# Display.net
KiCad netlist of a schematic drawn in EAGLE
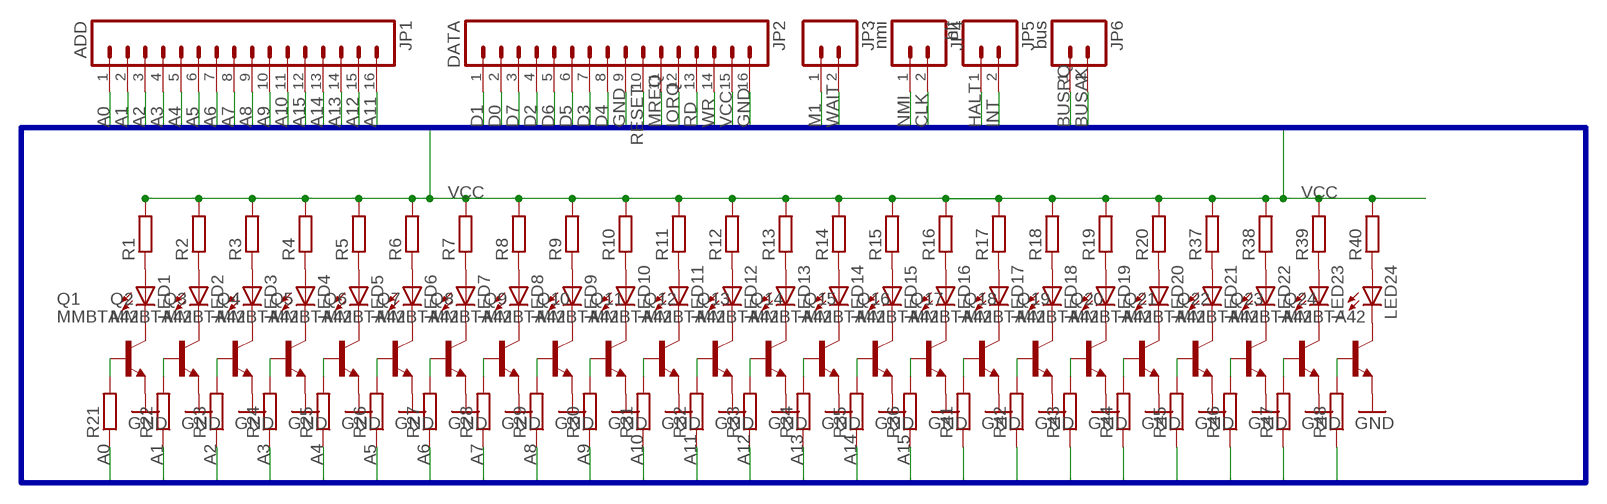
[diagram p0: schematic, sheet 1]

(export (version "E")
  (design (tool "Eeschema 10.0.6"))
  (components
    (comp (ref "JP1")
      (value "ADD")
      (footprint "eagle-import:1X16")
      (libsource (lib "eagle-import") (part "M16PTH"))
    )
    (comp (ref "JP2")
      (value "DATA")
      (footprint "eagle-import:1X16")
      (libsource (lib "eagle-import") (part "M16PTH"))
    )
    (comp (ref "JP3")
      (value "M02PTH")
      (footprint "eagle-import:1X02")
      (libsource (lib "eagle-import") (part "M02PTH"))
    )
    (comp (ref "JP4")
      (value "nmi")
      (footprint "eagle-import:1X02")
      (libsource (lib "eagle-import") (part "M02PTH"))
    )
    (comp (ref "JP5")
      (value "hlt")
      (footprint "eagle-import:1X02")
      (libsource (lib "eagle-import") (part "M02PTH"))
    )
    (comp (ref "JP6")
      (value "bus")
      (footprint "eagle-import:1X02")
      (libsource (lib "eagle-import") (part "M02PTH"))
    )
    (comp (ref "LED1")
      (value "LEDCHIP-LED0805")
      (footprint "eagle-import:CHIP-LED0805")
      (libsource (lib "eagle-import") (part "LEDCHIP-LED0805"))
    )
    (comp (ref "LED2")
      (value "LEDCHIP-LED0805")
      (footprint "eagle-import:CHIP-LED0805")
      (libsource (lib "eagle-import") (part "LEDCHIP-LED0805"))
    )
    (comp (ref "LED3")
      (value "LEDCHIP-LED0805")
      (footprint "eagle-import:CHIP-LED0805")
      (libsource (lib "eagle-import") (part "LEDCHIP-LED0805"))
    )
    (comp (ref "LED4")
      (value "LEDCHIP-LED0805")
      (footprint "eagle-import:CHIP-LED0805")
      (libsource (lib "eagle-import") (part "LEDCHIP-LED0805"))
    )
    (comp (ref "LED5")
      (value "LEDCHIP-LED0805")
      (footprint "eagle-import:CHIP-LED0805")
      (libsource (lib "eagle-import") (part "LEDCHIP-LED0805"))
    )
    (comp (ref "LED6")
      (value "LEDCHIP-LED0805")
      (footprint "eagle-import:CHIP-LED0805")
      (libsource (lib "eagle-import") (part "LEDCHIP-LED0805"))
    )
    (comp (ref "LED7")
      (value "LEDCHIP-LED0805")
      (footprint "eagle-import:CHIP-LED0805")
      (libsource (lib "eagle-import") (part "LEDCHIP-LED0805"))
    )
    (comp (ref "LED8")
      (value "LEDCHIP-LED0805")
      (footprint "eagle-import:CHIP-LED0805")
      (libsource (lib "eagle-import") (part "LEDCHIP-LED0805"))
    )
    (comp (ref "LED9")
      (value "LEDCHIP-LED0805")
      (footprint "eagle-import:CHIP-LED0805")
      (libsource (lib "eagle-import") (part "LEDCHIP-LED0805"))
    )
    (comp (ref "LED10")
      (value "LEDCHIP-LED0805")
      (footprint "eagle-import:CHIP-LED0805")
      (libsource (lib "eagle-import") (part "LEDCHIP-LED0805"))
    )
    (comp (ref "LED11")
      (value "LEDCHIP-LED0805")
      (footprint "eagle-import:CHIP-LED0805")
      (libsource (lib "eagle-import") (part "LEDCHIP-LED0805"))
    )
    (comp (ref "LED12")
      (value "LEDCHIP-LED0805")
      (footprint "eagle-import:CHIP-LED0805")
      (libsource (lib "eagle-import") (part "LEDCHIP-LED0805"))
    )
    (comp (ref "LED13")
      (value "LEDCHIP-LED0805")
      (footprint "eagle-import:CHIP-LED0805")
      (libsource (lib "eagle-import") (part "LEDCHIP-LED0805"))
    )
    (comp (ref "LED14")
      (value "LEDCHIP-LED0805")
      (footprint "eagle-import:CHIP-LED0805")
      (libsource (lib "eagle-import") (part "LEDCHIP-LED0805"))
    )
    (comp (ref "LED15")
      (value "LEDCHIP-LED0805")
      (footprint "eagle-import:CHIP-LED0805")
      (libsource (lib "eagle-import") (part "LEDCHIP-LED0805"))
    )
    (comp (ref "LED16")
      (value "LEDCHIP-LED0805")
      (footprint "eagle-import:CHIP-LED0805")
      (libsource (lib "eagle-import") (part "LEDCHIP-LED0805"))
    )
    (comp (ref "LED17")
      (value "LEDCHIP-LED0805")
      (footprint "eagle-import:CHIP-LED0805")
      (libsource (lib "eagle-import") (part "LEDCHIP-LED0805"))
    )
    (comp (ref "LED18")
      (value "LEDCHIP-LED0805")
      (footprint "eagle-import:CHIP-LED0805")
      (libsource (lib "eagle-import") (part "LEDCHIP-LED0805"))
    )
    (comp (ref "LED19")
      (value "LEDCHIP-LED0805")
      (footprint "eagle-import:CHIP-LED0805")
      (libsource (lib "eagle-import") (part "LEDCHIP-LED0805"))
    )
    (comp (ref "LED20")
      (value "LEDCHIP-LED0805")
      (footprint "eagle-import:CHIP-LED0805")
      (libsource (lib "eagle-import") (part "LEDCHIP-LED0805"))
    )
    (comp (ref "LED21")
      (value "LEDCHIP-LED0805")
      (footprint "eagle-import:CHIP-LED0805")
      (libsource (lib "eagle-import") (part "LEDCHIP-LED0805"))
    )
    (comp (ref "LED22")
      (value "LEDCHIP-LED0805")
      (footprint "eagle-import:CHIP-LED0805")
      (libsource (lib "eagle-import") (part "LEDCHIP-LED0805"))
    )
    (comp (ref "LED23")
      (value "LEDCHIP-LED0805")
      (footprint "eagle-import:CHIP-LED0805")
      (libsource (lib "eagle-import") (part "LEDCHIP-LED0805"))
    )
    (comp (ref "LED24")
      (value "LEDCHIP-LED0805")
      (footprint "eagle-import:CHIP-LED0805")
      (libsource (lib "eagle-import") (part "LEDCHIP-LED0805"))
    )
    (comp (ref "Q1")
      (value "MMBTA42")
      (footprint "eagle-import:SOT23")
      (libsource (lib "eagle-import") (part "MMBTA42"))
    )
    (comp (ref "Q2")
      (value "MMBTA42")
      (footprint "eagle-import:SOT23")
      (libsource (lib "eagle-import") (part "MMBTA42"))
    )
    (comp (ref "Q3")
      (value "MMBTA42")
      (footprint "eagle-import:SOT23")
      (libsource (lib "eagle-import") (part "MMBTA42"))
    )
    (comp (ref "Q4")
      (value "MMBTA42")
      (footprint "eagle-import:SOT23")
      (libsource (lib "eagle-import") (part "MMBTA42"))
    )
    (comp (ref "Q5")
      (value "MMBTA42")
      (footprint "eagle-import:SOT23")
      (libsource (lib "eagle-import") (part "MMBTA42"))
    )
    (comp (ref "Q6")
      (value "MMBTA42")
      (footprint "eagle-import:SOT23")
      (libsource (lib "eagle-import") (part "MMBTA42"))
    )
    (comp (ref "Q7")
      (value "MMBTA42")
      (footprint "eagle-import:SOT23")
      (libsource (lib "eagle-import") (part "MMBTA42"))
    )
    (comp (ref "Q8")
      (value "MMBTA42")
      (footprint "eagle-import:SOT23")
      (libsource (lib "eagle-import") (part "MMBTA42"))
    )
    (comp (ref "Q9")
      (value "MMBTA42")
      (footprint "eagle-import:SOT23")
      (libsource (lib "eagle-import") (part "MMBTA42"))
    )
    (comp (ref "Q10")
      (value "MMBTA42")
      (footprint "eagle-import:SOT23")
      (libsource (lib "eagle-import") (part "MMBTA42"))
    )
    (comp (ref "Q11")
      (value "MMBTA42")
      (footprint "eagle-import:SOT23")
      (libsource (lib "eagle-import") (part "MMBTA42"))
    )
    (comp (ref "Q12")
      (value "MMBTA42")
      (footprint "eagle-import:SOT23")
      (libsource (lib "eagle-import") (part "MMBTA42"))
    )
    (comp (ref "Q13")
      (value "MMBTA42")
      (footprint "eagle-import:SOT23")
      (libsource (lib "eagle-import") (part "MMBTA42"))
    )
    (comp (ref "Q14")
      (value "MMBTA42")
      (footprint "eagle-import:SOT23")
      (libsource (lib "eagle-import") (part "MMBTA42"))
    )
    (comp (ref "Q15")
      (value "MMBTA42")
      (footprint "eagle-import:SOT23")
      (libsource (lib "eagle-import") (part "MMBTA42"))
    )
    (comp (ref "Q16")
      (value "MMBTA42")
      (footprint "eagle-import:SOT23")
      (libsource (lib "eagle-import") (part "MMBTA42"))
    )
    (comp (ref "Q17")
      (value "MMBTA42")
      (footprint "eagle-import:SOT23")
      (libsource (lib "eagle-import") (part "MMBTA42"))
    )
    (comp (ref "Q18")
      (value "MMBTA42")
      (footprint "eagle-import:SOT23")
      (libsource (lib "eagle-import") (part "MMBTA42"))
    )
    (comp (ref "Q19")
      (value "MMBTA42")
      (footprint "eagle-import:SOT23")
      (libsource (lib "eagle-import") (part "MMBTA42"))
    )
    (comp (ref "Q20")
      (value "MMBTA42")
      (footprint "eagle-import:SOT23")
      (libsource (lib "eagle-import") (part "MMBTA42"))
    )
    (comp (ref "Q21")
      (value "MMBTA42")
      (footprint "eagle-import:SOT23")
      (libsource (lib "eagle-import") (part "MMBTA42"))
    )
    (comp (ref "Q22")
      (value "MMBTA42")
      (footprint "eagle-import:SOT23")
      (libsource (lib "eagle-import") (part "MMBTA42"))
    )
    (comp (ref "Q23")
      (value "MMBTA42")
      (footprint "eagle-import:SOT23")
      (libsource (lib "eagle-import") (part "MMBTA42"))
    )
    (comp (ref "Q24")
      (value "MMBTA42")
      (footprint "eagle-import:SOT23")
      (libsource (lib "eagle-import") (part "MMBTA42"))
    )
    (comp (ref "R1")
      (value "R-EU_M0805")
      (footprint "eagle-import:M0805")
      (libsource (lib "eagle-import") (part "R-EU_M0805"))
    )
    (comp (ref "R2")
      (value "R-EU_M0805")
      (footprint "eagle-import:M0805")
      (libsource (lib "eagle-import") (part "R-EU_M0805"))
    )
    (comp (ref "R3")
      (value "R-EU_M0805")
      (footprint "eagle-import:M0805")
      (libsource (lib "eagle-import") (part "R-EU_M0805"))
    )
    (comp (ref "R4")
      (value "R-EU_M0805")
      (footprint "eagle-import:M0805")
      (libsource (lib "eagle-import") (part "R-EU_M0805"))
    )
    (comp (ref "R5")
      (value "R-EU_M0805")
      (footprint "eagle-import:M0805")
      (libsource (lib "eagle-import") (part "R-EU_M0805"))
    )
    (comp (ref "R6")
      (value "R-EU_M0805")
      (footprint "eagle-import:M0805")
      (libsource (lib "eagle-import") (part "R-EU_M0805"))
    )
    (comp (ref "R7")
      (value "R-EU_M0805")
      (footprint "eagle-import:M0805")
      (libsource (lib "eagle-import") (part "R-EU_M0805"))
    )
    (comp (ref "R8")
      (value "R-EU_M0805")
      (footprint "eagle-import:M0805")
      (libsource (lib "eagle-import") (part "R-EU_M0805"))
    )
    (comp (ref "R9")
      (value "R-EU_M0805")
      (footprint "eagle-import:M0805")
      (libsource (lib "eagle-import") (part "R-EU_M0805"))
    )
    (comp (ref "R10")
      (value "R-EU_M0805")
      (footprint "eagle-import:M0805")
      (libsource (lib "eagle-import") (part "R-EU_M0805"))
    )
    (comp (ref "R11")
      (value "R-EU_M0805")
      (footprint "eagle-import:M0805")
      (libsource (lib "eagle-import") (part "R-EU_M0805"))
    )
    (comp (ref "R12")
      (value "R-EU_M0805")
      (footprint "eagle-import:M0805")
      (libsource (lib "eagle-import") (part "R-EU_M0805"))
    )
    (comp (ref "R13")
      (value "R-EU_M0805")
      (footprint "eagle-import:M0805")
      (libsource (lib "eagle-import") (part "R-EU_M0805"))
    )
    (comp (ref "R14")
      (value "R-EU_M0805")
      (footprint "eagle-import:M0805")
      (libsource (lib "eagle-import") (part "R-EU_M0805"))
    )
    (comp (ref "R15")
      (value "R-EU_M0805")
      (footprint "eagle-import:M0805")
      (libsource (lib "eagle-import") (part "R-EU_M0805"))
    )
    (comp (ref "R16")
      (value "R-EU_M0805")
      (footprint "eagle-import:M0805")
      (libsource (lib "eagle-import") (part "R-EU_M0805"))
    )
    (comp (ref "R17")
      (value "R-EU_M0805")
      (footprint "eagle-import:M0805")
      (libsource (lib "eagle-import") (part "R-EU_M0805"))
    )
    (comp (ref "R18")
      (value "R-EU_M0805")
      (footprint "eagle-import:M0805")
      (libsource (lib "eagle-import") (part "R-EU_M0805"))
    )
    (comp (ref "R19")
      (value "R-EU_M0805")
      (footprint "eagle-import:M0805")
      (libsource (lib "eagle-import") (part "R-EU_M0805"))
    )
    (comp (ref "R20")
      (value "R-EU_M0805")
      (footprint "eagle-import:M0805")
      (libsource (lib "eagle-import") (part "R-EU_M0805"))
    )
    (comp (ref "R21")
      (value "R-EU_M0805")
      (footprint "eagle-import:M0805")
      (libsource (lib "eagle-import") (part "R-EU_M0805"))
    )
    (comp (ref "R22")
      (value "R-EU_M0805")
      (footprint "eagle-import:M0805")
      (libsource (lib "eagle-import") (part "R-EU_M0805"))
    )
    (comp (ref "R23")
      (value "R-EU_M0805")
      (footprint "eagle-import:M0805")
      (libsource (lib "eagle-import") (part "R-EU_M0805"))
    )
    (comp (ref "R24")
      (value "R-EU_M0805")
      (footprint "eagle-import:M0805")
      (libsource (lib "eagle-import") (part "R-EU_M0805"))
    )
    (comp (ref "R25")
      (value "R-EU_M0805")
      (footprint "eagle-import:M0805")
      (libsource (lib "eagle-import") (part "R-EU_M0805"))
    )
    (comp (ref "R26")
      (value "R-EU_M0805")
      (footprint "eagle-import:M0805")
      (libsource (lib "eagle-import") (part "R-EU_M0805"))
    )
    (comp (ref "R27")
      (value "R-EU_M0805")
      (footprint "eagle-import:M0805")
      (libsource (lib "eagle-import") (part "R-EU_M0805"))
    )
    (comp (ref "R28")
      (value "R-EU_M0805")
      (footprint "eagle-import:M0805")
      (libsource (lib "eagle-import") (part "R-EU_M0805"))
    )
    (comp (ref "R29")
      (value "R-EU_M0805")
      (footprint "eagle-import:M0805")
      (libsource (lib "eagle-import") (part "R-EU_M0805"))
    )
    (comp (ref "R30")
      (value "R-EU_M0805")
      (footprint "eagle-import:M0805")
      (libsource (lib "eagle-import") (part "R-EU_M0805"))
    )
    (comp (ref "R31")
      (value "R-EU_M0805")
      (footprint "eagle-import:M0805")
      (libsource (lib "eagle-import") (part "R-EU_M0805"))
    )
    (comp (ref "R32")
      (value "R-EU_M0805")
      (footprint "eagle-import:M0805")
      (libsource (lib "eagle-import") (part "R-EU_M0805"))
    )
    (comp (ref "R33")
      (value "R-EU_M0805")
      (footprint "eagle-import:M0805")
      (libsource (lib "eagle-import") (part "R-EU_M0805"))
    )
    (comp (ref "R34")
      (value "R-EU_M0805")
      (footprint "eagle-import:M0805")
      (libsource (lib "eagle-import") (part "R-EU_M0805"))
    )
    (comp (ref "R35")
      (value "R-EU_M0805")
      (footprint "eagle-import:M0805")
      (libsource (lib "eagle-import") (part "R-EU_M0805"))
    )
    (comp (ref "R36")
      (value "R-EU_M0805")
      (footprint "eagle-import:M0805")
      (libsource (lib "eagle-import") (part "R-EU_M0805"))
    )
    (comp (ref "R37")
      (value "R-EU_M0805")
      (footprint "eagle-import:M0805")
      (libsource (lib "eagle-import") (part "R-EU_M0805"))
    )
    (comp (ref "R38")
      (value "R-EU_M0805")
      (footprint "eagle-import:M0805")
      (libsource (lib "eagle-import") (part "R-EU_M0805"))
    )
    (comp (ref "R39")
      (value "R-EU_M0805")
      (footprint "eagle-import:M0805")
      (libsource (lib "eagle-import") (part "R-EU_M0805"))
    )
    (comp (ref "R40")
      (value "R-EU_M0805")
      (footprint "eagle-import:M0805")
      (libsource (lib "eagle-import") (part "R-EU_M0805"))
    )
    (comp (ref "R41")
      (value "R-EU_M0805")
      (footprint "eagle-import:M0805")
      (libsource (lib "eagle-import") (part "R-EU_M0805"))
    )
    (comp (ref "R42")
      (value "R-EU_M0805")
      (footprint "eagle-import:M0805")
      (libsource (lib "eagle-import") (part "R-EU_M0805"))
    )
    (comp (ref "R43")
      (value "R-EU_M0805")
      (footprint "eagle-import:M0805")
      (libsource (lib "eagle-import") (part "R-EU_M0805"))
    )
    (comp (ref "R44")
      (value "R-EU_M0805")
      (footprint "eagle-import:M0805")
      (libsource (lib "eagle-import") (part "R-EU_M0805"))
    )
    (comp (ref "R45")
      (value "R-EU_M0805")
      (footprint "eagle-import:M0805")
      (libsource (lib "eagle-import") (part "R-EU_M0805"))
    )
    (comp (ref "R46")
      (value "R-EU_M0805")
      (footprint "eagle-import:M0805")
      (libsource (lib "eagle-import") (part "R-EU_M0805"))
    )
    (comp (ref "R47")
      (value "R-EU_M0805")
      (footprint "eagle-import:M0805")
      (libsource (lib "eagle-import") (part "R-EU_M0805"))
    )
    (comp (ref "R48")
      (value "R-EU_M0805")
      (footprint "eagle-import:M0805")
      (libsource (lib "eagle-import") (part "R-EU_M0805"))
    )
  )
  (nets
    (net (code "1") (name "/A0") (class "Default")
      (node (ref "JP1") (pin "1") (pinfunction "1_1") (pintype "passive"))
      (node (ref "R21") (pin "1") (pinfunction "1_1") (pintype "passive"))
    )
    (net (code "2") (name "/A1") (class "Default")
      (node (ref "JP1") (pin "2") (pinfunction "2_2") (pintype "passive"))
      (node (ref "R22") (pin "1") (pinfunction "1_1") (pintype "passive"))
    )
    (net (code "3") (name "/A2") (class "Default")
      (node (ref "JP1") (pin "3") (pinfunction "3_3") (pintype "passive"))
      (node (ref "R23") (pin "1") (pinfunction "1_1") (pintype "passive"))
    )
    (net (code "4") (name "/A3") (class "Default")
      (node (ref "JP1") (pin "4") (pinfunction "4_4") (pintype "passive"))
      (node (ref "R24") (pin "1") (pinfunction "1_1") (pintype "passive"))
    )
    (net (code "5") (name "/A4") (class "Default")
      (node (ref "JP1") (pin "5") (pinfunction "5_5") (pintype "passive"))
      (node (ref "R25") (pin "1") (pinfunction "1_1") (pintype "passive"))
    )
    (net (code "6") (name "/A5") (class "Default")
      (node (ref "JP1") (pin "6") (pinfunction "6_6") (pintype "passive"))
      (node (ref "R26") (pin "1") (pinfunction "1_1") (pintype "passive"))
    )
    (net (code "7") (name "/A6") (class "Default")
      (node (ref "JP1") (pin "7") (pinfunction "7_7") (pintype "passive"))
      (node (ref "R27") (pin "1") (pinfunction "1_1") (pintype "passive"))
    )
    (net (code "8") (name "/A7") (class "Default")
      (node (ref "JP1") (pin "8") (pinfunction "8_8") (pintype "passive"))
      (node (ref "R28") (pin "1") (pinfunction "1_1") (pintype "passive"))
    )
    (net (code "9") (name "/A8") (class "Default")
      (node (ref "JP1") (pin "9") (pinfunction "9_9") (pintype "passive"))
      (node (ref "R29") (pin "1") (pinfunction "1_1") (pintype "passive"))
    )
    (net (code "10") (name "/A9") (class "Default")
      (node (ref "JP1") (pin "10") (pinfunction "10_10") (pintype "passive"))
      (node (ref "R30") (pin "1") (pinfunction "1_1") (pintype "passive"))
    )
    (net (code "11") (name "/A10") (class "Default")
      (node (ref "JP1") (pin "11") (pinfunction "11_11") (pintype "passive"))
      (node (ref "R31") (pin "1") (pinfunction "1_1") (pintype "passive"))
    )
    (net (code "12") (name "/A11") (class "Default")
      (node (ref "JP1") (pin "16") (pinfunction "16_16") (pintype "passive"))
      (node (ref "R32") (pin "1") (pinfunction "1_1") (pintype "passive"))
    )
    (net (code "13") (name "/A12") (class "Default")
      (node (ref "JP1") (pin "15") (pinfunction "15_15") (pintype "passive"))
      (node (ref "R33") (pin "1") (pinfunction "1_1") (pintype "passive"))
    )
    (net (code "14") (name "/A13") (class "Default")
      (node (ref "JP1") (pin "14") (pinfunction "14_14") (pintype "passive"))
      (node (ref "R34") (pin "1") (pinfunction "1_1") (pintype "passive"))
    )
    (net (code "15") (name "/A14") (class "Default")
      (node (ref "JP1") (pin "13") (pinfunction "13_13") (pintype "passive"))
      (node (ref "R35") (pin "1") (pinfunction "1_1") (pintype "passive"))
    )
    (net (code "16") (name "/A15") (class "Default")
      (node (ref "JP1") (pin "12") (pinfunction "12_12") (pintype "passive"))
      (node (ref "R36") (pin "1") (pinfunction "1_1") (pintype "passive"))
    )
    (net (code "17") (name "/BUSAK") (class "Default")
      (node (ref "JP6") (pin "2") (pinfunction "2_2") (pintype "passive"))
    )
    (net (code "18") (name "/BUSRQ") (class "Default")
      (node (ref "JP6") (pin "1") (pinfunction "1_1") (pintype "passive"))
    )
    (net (code "19") (name "/CLK") (class "Default")
      (node (ref "JP4") (pin "2") (pinfunction "2_2") (pintype "passive"))
    )
    (net (code "20") (name "/D0") (class "Default")
      (node (ref "JP2") (pin "2") (pinfunction "2_2") (pintype "passive"))
      (node (ref "R41") (pin "1") (pinfunction "1_1") (pintype "passive"))
    )
    (net (code "21") (name "/D1") (class "Default")
      (node (ref "JP2") (pin "1") (pinfunction "1_1") (pintype "passive"))
      (node (ref "R42") (pin "1") (pinfunction "1_1") (pintype "passive"))
    )
    (net (code "22") (name "/D2") (class "Default")
      (node (ref "JP2") (pin "4") (pinfunction "4_4") (pintype "passive"))
      (node (ref "R43") (pin "1") (pinfunction "1_1") (pintype "passive"))
    )
    (net (code "23") (name "/D3") (class "Default")
      (node (ref "JP2") (pin "7") (pinfunction "7_7") (pintype "passive"))
      (node (ref "R44") (pin "1") (pinfunction "1_1") (pintype "passive"))
    )
    (net (code "24") (name "/D4") (class "Default")
      (node (ref "JP2") (pin "8") (pinfunction "8_8") (pintype "passive"))
      (node (ref "R45") (pin "1") (pinfunction "1_1") (pintype "passive"))
    )
    (net (code "25") (name "/D5") (class "Default")
      (node (ref "JP2") (pin "6") (pinfunction "6_6") (pintype "passive"))
      (node (ref "R46") (pin "1") (pinfunction "1_1") (pintype "passive"))
    )
    (net (code "26") (name "/D6") (class "Default")
      (node (ref "JP2") (pin "5") (pinfunction "5_5") (pintype "passive"))
      (node (ref "R47") (pin "1") (pinfunction "1_1") (pintype "passive"))
    )
    (net (code "27") (name "/D7") (class "Default")
      (node (ref "JP2") (pin "3") (pinfunction "3_3") (pintype "passive"))
      (node (ref "R48") (pin "1") (pinfunction "1_1") (pintype "passive"))
    )
    (net (code "28") (name "/HALT") (class "Default")
      (node (ref "JP5") (pin "1") (pinfunction "1_1") (pintype "passive"))
    )
    (net (code "29") (name "/INT") (class "Default")
      (node (ref "JP5") (pin "2") (pinfunction "2_2") (pintype "passive"))
    )
    (net (code "30") (name "/IORQ") (class "Default")
      (node (ref "JP2") (pin "12") (pinfunction "12_12") (pintype "passive"))
    )
    (net (code "31") (name "/M1") (class "Default")
      (node (ref "JP3") (pin "1") (pinfunction "1_1") (pintype "passive"))
    )
    (net (code "32") (name "/MREQ") (class "Default")
      (node (ref "JP2") (pin "11") (pinfunction "11_11") (pintype "passive"))
    )
    (net (code "33") (name "/NMI") (class "Default")
      (node (ref "JP4") (pin "1") (pinfunction "1_1") (pintype "passive"))
    )
    (net (code "34") (name "/RD") (class "Default")
      (node (ref "JP2") (pin "13") (pinfunction "13_13") (pintype "passive"))
    )
    (net (code "35") (name "/RESET") (class "Default")
      (node (ref "JP2") (pin "10") (pinfunction "10_10") (pintype "passive"))
    )
    (net (code "36") (name "/VCC") (class "Default")
      (node (ref "JP2") (pin "15") (pinfunction "15_15") (pintype "passive"))
      (node (ref "R1") (pin "2") (pinfunction "2_2") (pintype "passive"))
      (node (ref "R10") (pin "2") (pinfunction "2_2") (pintype "passive"))
      (node (ref "R11") (pin "2") (pinfunction "2_2") (pintype "passive"))
      (node (ref "R12") (pin "2") (pinfunction "2_2") (pintype "passive"))
      (node (ref "R13") (pin "2") (pinfunction "2_2") (pintype "passive"))
      (node (ref "R14") (pin "2") (pinfunction "2_2") (pintype "passive"))
      (node (ref "R15") (pin "2") (pinfunction "2_2") (pintype "passive"))
      (node (ref "R16") (pin "2") (pinfunction "2_2") (pintype "passive"))
      (node (ref "R17") (pin "2") (pinfunction "2_2") (pintype "passive"))
      (node (ref "R18") (pin "2") (pinfunction "2_2") (pintype "passive"))
      (node (ref "R19") (pin "2") (pinfunction "2_2") (pintype "passive"))
      (node (ref "R2") (pin "2") (pinfunction "2_2") (pintype "passive"))
      (node (ref "R20") (pin "2") (pinfunction "2_2") (pintype "passive"))
      (node (ref "R3") (pin "2") (pinfunction "2_2") (pintype "passive"))
      (node (ref "R37") (pin "2") (pinfunction "2_2") (pintype "passive"))
      (node (ref "R38") (pin "2") (pinfunction "2_2") (pintype "passive"))
      (node (ref "R39") (pin "2") (pinfunction "2_2") (pintype "passive"))
      (node (ref "R4") (pin "2") (pinfunction "2_2") (pintype "passive"))
      (node (ref "R40") (pin "2") (pinfunction "2_2") (pintype "passive"))
      (node (ref "R5") (pin "2") (pinfunction "2_2") (pintype "passive"))
      (node (ref "R6") (pin "2") (pinfunction "2_2") (pintype "passive"))
      (node (ref "R7") (pin "2") (pinfunction "2_2") (pintype "passive"))
      (node (ref "R8") (pin "2") (pinfunction "2_2") (pintype "passive"))
      (node (ref "R9") (pin "2") (pinfunction "2_2") (pintype "passive"))
    )
    (net (code "37") (name "/WAIT") (class "Default")
      (node (ref "JP3") (pin "2") (pinfunction "2_2") (pintype "passive"))
    )
    (net (code "38") (name "/WR") (class "Default")
      (node (ref "JP2") (pin "14") (pinfunction "14_14") (pintype "passive"))
    )
    (net (code "39") (name "GND") (class "Default")
      (node (ref "JP2") (pin "16") (pinfunction "16_16") (pintype "passive"))
      (node (ref "JP2") (pin "9") (pinfunction "9_9") (pintype "passive"))
      (node (ref "Q1") (pin "2") (pinfunction "E_2") (pintype "passive"))
      (node (ref "Q10") (pin "2") (pinfunction "E_2") (pintype "passive"))
      (node (ref "Q11") (pin "2") (pinfunction "E_2") (pintype "passive"))
      (node (ref "Q12") (pin "2") (pinfunction "E_2") (pintype "passive"))
      (node (ref "Q13") (pin "2") (pinfunction "E_2") (pintype "passive"))
      (node (ref "Q14") (pin "2") (pinfunction "E_2") (pintype "passive"))
      (node (ref "Q15") (pin "2") (pinfunction "E_2") (pintype "passive"))
      (node (ref "Q16") (pin "2") (pinfunction "E_2") (pintype "passive"))
      (node (ref "Q17") (pin "2") (pinfunction "E_2") (pintype "passive"))
      (node (ref "Q18") (pin "2") (pinfunction "E_2") (pintype "passive"))
      (node (ref "Q19") (pin "2") (pinfunction "E_2") (pintype "passive"))
      (node (ref "Q2") (pin "2") (pinfunction "E_2") (pintype "passive"))
      (node (ref "Q20") (pin "2") (pinfunction "E_2") (pintype "passive"))
      (node (ref "Q21") (pin "2") (pinfunction "E_2") (pintype "passive"))
      (node (ref "Q22") (pin "2") (pinfunction "E_2") (pintype "passive"))
      (node (ref "Q23") (pin "2") (pinfunction "E_2") (pintype "passive"))
      (node (ref "Q24") (pin "2") (pinfunction "E_2") (pintype "passive"))
      (node (ref "Q3") (pin "2") (pinfunction "E_2") (pintype "passive"))
      (node (ref "Q4") (pin "2") (pinfunction "E_2") (pintype "passive"))
      (node (ref "Q5") (pin "2") (pinfunction "E_2") (pintype "passive"))
      (node (ref "Q6") (pin "2") (pinfunction "E_2") (pintype "passive"))
      (node (ref "Q7") (pin "2") (pinfunction "E_2") (pintype "passive"))
      (node (ref "Q8") (pin "2") (pinfunction "E_2") (pintype "passive"))
      (node (ref "Q9") (pin "2") (pinfunction "E_2") (pintype "passive"))
    )
    (net (code "40") (name "Net-(LED1-PadA)") (class "Default")
      (node (ref "LED1") (pin "A") (pinfunction "A_A") (pintype "passive"))
      (node (ref "R1") (pin "1") (pinfunction "1_1") (pintype "passive"))
    )
    (net (code "41") (name "Net-(LED2-PadA)") (class "Default")
      (node (ref "LED2") (pin "A") (pinfunction "A_A") (pintype "passive"))
      (node (ref "R2") (pin "1") (pinfunction "1_1") (pintype "passive"))
    )
    (net (code "42") (name "Net-(LED3-PadA)") (class "Default")
      (node (ref "LED3") (pin "A") (pinfunction "A_A") (pintype "passive"))
      (node (ref "R3") (pin "1") (pinfunction "1_1") (pintype "passive"))
    )
    (net (code "43") (name "Net-(LED4-PadA)") (class "Default")
      (node (ref "LED4") (pin "A") (pinfunction "A_A") (pintype "passive"))
      (node (ref "R4") (pin "1") (pinfunction "1_1") (pintype "passive"))
    )
    (net (code "44") (name "Net-(LED5-PadA)") (class "Default")
      (node (ref "LED5") (pin "A") (pinfunction "A_A") (pintype "passive"))
      (node (ref "R5") (pin "1") (pinfunction "1_1") (pintype "passive"))
    )
    (net (code "45") (name "Net-(LED6-PadA)") (class "Default")
      (node (ref "LED6") (pin "A") (pinfunction "A_A") (pintype "passive"))
      (node (ref "R6") (pin "1") (pinfunction "1_1") (pintype "passive"))
    )
    (net (code "46") (name "Net-(LED7-PadA)") (class "Default")
      (node (ref "LED7") (pin "A") (pinfunction "A_A") (pintype "passive"))
      (node (ref "R7") (pin "1") (pinfunction "1_1") (pintype "passive"))
    )
    (net (code "47") (name "Net-(LED8-PadA)") (class "Default")
      (node (ref "LED8") (pin "A") (pinfunction "A_A") (pintype "passive"))
      (node (ref "R8") (pin "1") (pinfunction "1_1") (pintype "passive"))
    )
    (net (code "48") (name "Net-(LED9-PadA)") (class "Default")
      (node (ref "LED9") (pin "A") (pinfunction "A_A") (pintype "passive"))
      (node (ref "R9") (pin "1") (pinfunction "1_1") (pintype "passive"))
    )
    (net (code "49") (name "Net-(LED10-PadA)") (class "Default")
      (node (ref "LED10") (pin "A") (pinfunction "A_A") (pintype "passive"))
      (node (ref "R10") (pin "1") (pinfunction "1_1") (pintype "passive"))
    )
    (net (code "50") (name "Net-(LED11-PadA)") (class "Default")
      (node (ref "LED11") (pin "A") (pinfunction "A_A") (pintype "passive"))
      (node (ref "R11") (pin "1") (pinfunction "1_1") (pintype "passive"))
    )
    (net (code "51") (name "Net-(LED12-PadA)") (class "Default")
      (node (ref "LED12") (pin "A") (pinfunction "A_A") (pintype "passive"))
      (node (ref "R12") (pin "1") (pinfunction "1_1") (pintype "passive"))
    )
    (net (code "52") (name "Net-(LED13-PadA)") (class "Default")
      (node (ref "LED13") (pin "A") (pinfunction "A_A") (pintype "passive"))
      (node (ref "R13") (pin "1") (pinfunction "1_1") (pintype "passive"))
    )
    (net (code "53") (name "Net-(LED14-PadA)") (class "Default")
      (node (ref "LED14") (pin "A") (pinfunction "A_A") (pintype "passive"))
      (node (ref "R14") (pin "1") (pinfunction "1_1") (pintype "passive"))
    )
    (net (code "54") (name "Net-(LED15-PadA)") (class "Default")
      (node (ref "LED15") (pin "A") (pinfunction "A_A") (pintype "passive"))
      (node (ref "R15") (pin "1") (pinfunction "1_1") (pintype "passive"))
    )
    (net (code "55") (name "Net-(LED16-PadA)") (class "Default")
      (node (ref "LED16") (pin "A") (pinfunction "A_A") (pintype "passive"))
      (node (ref "R16") (pin "1") (pinfunction "1_1") (pintype "passive"))
    )
    (net (code "56") (name "Net-(LED17-PadA)") (class "Default")
      (node (ref "LED17") (pin "A") (pinfunction "A_A") (pintype "passive"))
      (node (ref "R17") (pin "1") (pinfunction "1_1") (pintype "passive"))
    )
    (net (code "57") (name "Net-(LED18-PadA)") (class "Default")
      (node (ref "LED18") (pin "A") (pinfunction "A_A") (pintype "passive"))
      (node (ref "R18") (pin "1") (pinfunction "1_1") (pintype "passive"))
    )
    (net (code "58") (name "Net-(LED19-PadA)") (class "Default")
      (node (ref "LED19") (pin "A") (pinfunction "A_A") (pintype "passive"))
      (node (ref "R19") (pin "1") (pinfunction "1_1") (pintype "passive"))
    )
    (net (code "59") (name "Net-(LED20-PadA)") (class "Default")
      (node (ref "LED20") (pin "A") (pinfunction "A_A") (pintype "passive"))
      (node (ref "R20") (pin "1") (pinfunction "1_1") (pintype "passive"))
    )
    (net (code "60") (name "Net-(LED21-PadA)") (class "Default")
      (node (ref "LED21") (pin "A") (pinfunction "A_A") (pintype "passive"))
      (node (ref "R37") (pin "1") (pinfunction "1_1") (pintype "passive"))
    )
    (net (code "61") (name "Net-(LED22-PadA)") (class "Default")
      (node (ref "LED22") (pin "A") (pinfunction "A_A") (pintype "passive"))
      (node (ref "R38") (pin "1") (pinfunction "1_1") (pintype "passive"))
    )
    (net (code "62") (name "Net-(LED23-PadA)") (class "Default")
      (node (ref "LED23") (pin "A") (pinfunction "A_A") (pintype "passive"))
      (node (ref "R39") (pin "1") (pinfunction "1_1") (pintype "passive"))
    )
    (net (code "63") (name "Net-(LED24-PadA)") (class "Default")
      (node (ref "LED24") (pin "A") (pinfunction "A_A") (pintype "passive"))
      (node (ref "R40") (pin "1") (pinfunction "1_1") (pintype "passive"))
    )
    (net (code "64") (name "Net-(Q1-B)") (class "Default")
      (node (ref "Q1") (pin "1") (pinfunction "B_1") (pintype "passive"))
      (node (ref "R21") (pin "2") (pinfunction "2_2") (pintype "passive"))
    )
    (net (code "65") (name "Net-(Q1-C)") (class "Default")
      (node (ref "LED1") (pin "C") (pinfunction "C_C") (pintype "passive"))
      (node (ref "Q1") (pin "3") (pinfunction "C_3") (pintype "passive"))
    )
    (net (code "66") (name "Net-(Q2-B)") (class "Default")
      (node (ref "Q2") (pin "1") (pinfunction "B_1") (pintype "passive"))
      (node (ref "R22") (pin "2") (pinfunction "2_2") (pintype "passive"))
    )
    (net (code "67") (name "Net-(Q2-C)") (class "Default")
      (node (ref "LED2") (pin "C") (pinfunction "C_C") (pintype "passive"))
      (node (ref "Q2") (pin "3") (pinfunction "C_3") (pintype "passive"))
    )
    (net (code "68") (name "Net-(Q3-B)") (class "Default")
      (node (ref "Q3") (pin "1") (pinfunction "B_1") (pintype "passive"))
      (node (ref "R23") (pin "2") (pinfunction "2_2") (pintype "passive"))
    )
    (net (code "69") (name "Net-(Q3-C)") (class "Default")
      (node (ref "LED3") (pin "C") (pinfunction "C_C") (pintype "passive"))
      (node (ref "Q3") (pin "3") (pinfunction "C_3") (pintype "passive"))
    )
    (net (code "70") (name "Net-(Q4-B)") (class "Default")
      (node (ref "Q4") (pin "1") (pinfunction "B_1") (pintype "passive"))
      (node (ref "R24") (pin "2") (pinfunction "2_2") (pintype "passive"))
    )
    (net (code "71") (name "Net-(Q4-C)") (class "Default")
      (node (ref "LED4") (pin "C") (pinfunction "C_C") (pintype "passive"))
      (node (ref "Q4") (pin "3") (pinfunction "C_3") (pintype "passive"))
    )
    (net (code "72") (name "Net-(Q5-B)") (class "Default")
      (node (ref "Q5") (pin "1") (pinfunction "B_1") (pintype "passive"))
      (node (ref "R25") (pin "2") (pinfunction "2_2") (pintype "passive"))
    )
    (net (code "73") (name "Net-(Q5-C)") (class "Default")
      (node (ref "LED5") (pin "C") (pinfunction "C_C") (pintype "passive"))
      (node (ref "Q5") (pin "3") (pinfunction "C_3") (pintype "passive"))
    )
    (net (code "74") (name "Net-(Q6-B)") (class "Default")
      (node (ref "Q6") (pin "1") (pinfunction "B_1") (pintype "passive"))
      (node (ref "R26") (pin "2") (pinfunction "2_2") (pintype "passive"))
    )
    (net (code "75") (name "Net-(Q6-C)") (class "Default")
      (node (ref "LED6") (pin "C") (pinfunction "C_C") (pintype "passive"))
      (node (ref "Q6") (pin "3") (pinfunction "C_3") (pintype "passive"))
    )
    (net (code "76") (name "Net-(Q7-B)") (class "Default")
      (node (ref "Q7") (pin "1") (pinfunction "B_1") (pintype "passive"))
      (node (ref "R27") (pin "2") (pinfunction "2_2") (pintype "passive"))
    )
    (net (code "77") (name "Net-(Q7-C)") (class "Default")
      (node (ref "LED7") (pin "C") (pinfunction "C_C") (pintype "passive"))
      (node (ref "Q7") (pin "3") (pinfunction "C_3") (pintype "passive"))
    )
    (net (code "78") (name "Net-(Q8-B)") (class "Default")
      (node (ref "Q8") (pin "1") (pinfunction "B_1") (pintype "passive"))
      (node (ref "R28") (pin "2") (pinfunction "2_2") (pintype "passive"))
    )
    (net (code "79") (name "Net-(Q8-C)") (class "Default")
      (node (ref "LED8") (pin "C") (pinfunction "C_C") (pintype "passive"))
      (node (ref "Q8") (pin "3") (pinfunction "C_3") (pintype "passive"))
    )
    (net (code "80") (name "Net-(Q9-B)") (class "Default")
      (node (ref "Q9") (pin "1") (pinfunction "B_1") (pintype "passive"))
      (node (ref "R29") (pin "2") (pinfunction "2_2") (pintype "passive"))
    )
    (net (code "81") (name "Net-(Q9-C)") (class "Default")
      (node (ref "LED9") (pin "C") (pinfunction "C_C") (pintype "passive"))
      (node (ref "Q9") (pin "3") (pinfunction "C_3") (pintype "passive"))
    )
    (net (code "82") (name "Net-(Q10-B)") (class "Default")
      (node (ref "Q10") (pin "1") (pinfunction "B_1") (pintype "passive"))
      (node (ref "R30") (pin "2") (pinfunction "2_2") (pintype "passive"))
    )
    (net (code "83") (name "Net-(Q10-C)") (class "Default")
      (node (ref "LED10") (pin "C") (pinfunction "C_C") (pintype "passive"))
      (node (ref "Q10") (pin "3") (pinfunction "C_3") (pintype "passive"))
    )
    (net (code "84") (name "Net-(Q11-B)") (class "Default")
      (node (ref "Q11") (pin "1") (pinfunction "B_1") (pintype "passive"))
      (node (ref "R31") (pin "2") (pinfunction "2_2") (pintype "passive"))
    )
    (net (code "85") (name "Net-(Q11-C)") (class "Default")
      (node (ref "LED11") (pin "C") (pinfunction "C_C") (pintype "passive"))
      (node (ref "Q11") (pin "3") (pinfunction "C_3") (pintype "passive"))
    )
    (net (code "86") (name "Net-(Q12-B)") (class "Default")
      (node (ref "Q12") (pin "1") (pinfunction "B_1") (pintype "passive"))
      (node (ref "R32") (pin "2") (pinfunction "2_2") (pintype "passive"))
    )
    (net (code "87") (name "Net-(Q12-C)") (class "Default")
      (node (ref "LED12") (pin "C") (pinfunction "C_C") (pintype "passive"))
      (node (ref "Q12") (pin "3") (pinfunction "C_3") (pintype "passive"))
    )
    (net (code "88") (name "Net-(Q13-B)") (class "Default")
      (node (ref "Q13") (pin "1") (pinfunction "B_1") (pintype "passive"))
      (node (ref "R33") (pin "2") (pinfunction "2_2") (pintype "passive"))
    )
    (net (code "89") (name "Net-(Q13-C)") (class "Default")
      (node (ref "LED13") (pin "C") (pinfunction "C_C") (pintype "passive"))
      (node (ref "Q13") (pin "3") (pinfunction "C_3") (pintype "passive"))
    )
    (net (code "90") (name "Net-(Q14-B)") (class "Default")
      (node (ref "Q14") (pin "1") (pinfunction "B_1") (pintype "passive"))
      (node (ref "R34") (pin "2") (pinfunction "2_2") (pintype "passive"))
    )
    (net (code "91") (name "Net-(Q14-C)") (class "Default")
      (node (ref "LED14") (pin "C") (pinfunction "C_C") (pintype "passive"))
      (node (ref "Q14") (pin "3") (pinfunction "C_3") (pintype "passive"))
    )
    (net (code "92") (name "Net-(Q15-B)") (class "Default")
      (node (ref "Q15") (pin "1") (pinfunction "B_1") (pintype "passive"))
      (node (ref "R35") (pin "2") (pinfunction "2_2") (pintype "passive"))
    )
    (net (code "93") (name "Net-(Q15-C)") (class "Default")
      (node (ref "LED15") (pin "C") (pinfunction "C_C") (pintype "passive"))
      (node (ref "Q15") (pin "3") (pinfunction "C_3") (pintype "passive"))
    )
    (net (code "94") (name "Net-(Q16-B)") (class "Default")
      (node (ref "Q16") (pin "1") (pinfunction "B_1") (pintype "passive"))
      (node (ref "R36") (pin "2") (pinfunction "2_2") (pintype "passive"))
    )
    (net (code "95") (name "Net-(Q16-C)") (class "Default")
      (node (ref "LED16") (pin "C") (pinfunction "C_C") (pintype "passive"))
      (node (ref "Q16") (pin "3") (pinfunction "C_3") (pintype "passive"))
    )
    (net (code "96") (name "Net-(Q17-B)") (class "Default")
      (node (ref "Q17") (pin "1") (pinfunction "B_1") (pintype "passive"))
      (node (ref "R41") (pin "2") (pinfunction "2_2") (pintype "passive"))
    )
    (net (code "97") (name "Net-(Q17-C)") (class "Default")
      (node (ref "LED17") (pin "C") (pinfunction "C_C") (pintype "passive"))
      (node (ref "Q17") (pin "3") (pinfunction "C_3") (pintype "passive"))
    )
    (net (code "98") (name "Net-(Q18-B)") (class "Default")
      (node (ref "Q18") (pin "1") (pinfunction "B_1") (pintype "passive"))
      (node (ref "R42") (pin "2") (pinfunction "2_2") (pintype "passive"))
    )
    (net (code "99") (name "Net-(Q18-C)") (class "Default")
      (node (ref "LED18") (pin "C") (pinfunction "C_C") (pintype "passive"))
      (node (ref "Q18") (pin "3") (pinfunction "C_3") (pintype "passive"))
    )
    (net (code "100") (name "Net-(Q19-B)") (class "Default")
      (node (ref "Q19") (pin "1") (pinfunction "B_1") (pintype "passive"))
      (node (ref "R43") (pin "2") (pinfunction "2_2") (pintype "passive"))
    )
    (net (code "101") (name "Net-(Q19-C)") (class "Default")
      (node (ref "LED19") (pin "C") (pinfunction "C_C") (pintype "passive"))
      (node (ref "Q19") (pin "3") (pinfunction "C_3") (pintype "passive"))
    )
    (net (code "102") (name "Net-(Q20-B)") (class "Default")
      (node (ref "Q20") (pin "1") (pinfunction "B_1") (pintype "passive"))
      (node (ref "R44") (pin "2") (pinfunction "2_2") (pintype "passive"))
    )
    (net (code "103") (name "Net-(Q20-C)") (class "Default")
      (node (ref "LED20") (pin "C") (pinfunction "C_C") (pintype "passive"))
      (node (ref "Q20") (pin "3") (pinfunction "C_3") (pintype "passive"))
    )
    (net (code "104") (name "Net-(Q21-B)") (class "Default")
      (node (ref "Q21") (pin "1") (pinfunction "B_1") (pintype "passive"))
      (node (ref "R45") (pin "2") (pinfunction "2_2") (pintype "passive"))
    )
    (net (code "105") (name "Net-(Q21-C)") (class "Default")
      (node (ref "LED21") (pin "C") (pinfunction "C_C") (pintype "passive"))
      (node (ref "Q21") (pin "3") (pinfunction "C_3") (pintype "passive"))
    )
    (net (code "106") (name "Net-(Q22-B)") (class "Default")
      (node (ref "Q22") (pin "1") (pinfunction "B_1") (pintype "passive"))
      (node (ref "R46") (pin "2") (pinfunction "2_2") (pintype "passive"))
    )
    (net (code "107") (name "Net-(Q22-C)") (class "Default")
      (node (ref "LED22") (pin "C") (pinfunction "C_C") (pintype "passive"))
      (node (ref "Q22") (pin "3") (pinfunction "C_3") (pintype "passive"))
    )
    (net (code "108") (name "Net-(Q23-B)") (class "Default")
      (node (ref "Q23") (pin "1") (pinfunction "B_1") (pintype "passive"))
      (node (ref "R47") (pin "2") (pinfunction "2_2") (pintype "passive"))
    )
    (net (code "109") (name "Net-(Q23-C)") (class "Default")
      (node (ref "LED23") (pin "C") (pinfunction "C_C") (pintype "passive"))
      (node (ref "Q23") (pin "3") (pinfunction "C_3") (pintype "passive"))
    )
    (net (code "110") (name "Net-(Q24-B)") (class "Default")
      (node (ref "Q24") (pin "1") (pinfunction "B_1") (pintype "passive"))
      (node (ref "R48") (pin "2") (pinfunction "2_2") (pintype "passive"))
    )
    (net (code "111") (name "Net-(Q24-C)") (class "Default")
      (node (ref "LED24") (pin "C") (pinfunction "C_C") (pintype "passive"))
      (node (ref "Q24") (pin "3") (pinfunction "C_3") (pintype "passive"))
    )
  )
)
